# IR_beacon.net
KiCad netlist of a schematic drawn in EAGLE
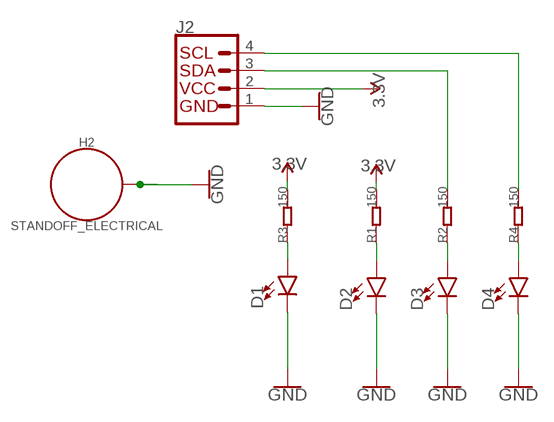
[diagram p0: schematic, sheet 1]

(export (version "E")
  (design (tool "Eeschema 10.0.6"))
  (components
    (comp (ref "D1")
      (value "LED-FKIT-1206")
      (footprint "eagle-import:FKIT-LED-1206")
      (libsource (lib "eagle-import") (part "LED-FKIT-1206"))
    )
    (comp (ref "D2")
      (value "LED-FKIT-1206")
      (footprint "eagle-import:FKIT-LED-1206")
      (libsource (lib "eagle-import") (part "LED-FKIT-1206"))
    )
    (comp (ref "D3")
      (value "LED-FKIT-1206")
      (footprint "eagle-import:FKIT-LED-1206")
      (libsource (lib "eagle-import") (part "LED-FKIT-1206"))
    )
    (comp (ref "D4")
      (value "LED-FKIT-1206")
      (footprint "eagle-import:FKIT-LED-1206")
      (libsource (lib "eagle-import") (part "LED-FKIT-1206"))
    )
    (comp (ref "H2")
      (value "STANDOFF_ELECTRICAL")
      (footprint "eagle-import:STANDOFF-ELECTRICAL")
      (libsource (lib "eagle-import") (part "STANDOFF_ELECTRICAL"))
    )
    (comp (ref "J2")
      (value "QWIIC_CONNECTORJS-1MM")
      (footprint "eagle-import:1X04_1MM_RA")
      (libsource (lib "eagle-import") (part "QWIIC_CONNECTORJS-1MM"))
    )
    (comp (ref "R1")
      (value "150")
      (footprint "eagle-import:0603_S")
      (libsource (lib "eagle-import") (part "005-R0603_S"))
    )
    (comp (ref "R2")
      (value "150")
      (footprint "eagle-import:0603_S")
      (libsource (lib "eagle-import") (part "005-R0603_S"))
    )
    (comp (ref "R3")
      (value "150")
      (footprint "eagle-import:0603_S")
      (libsource (lib "eagle-import") (part "005-R0603_S"))
    )
    (comp (ref "R4")
      (value "150")
      (footprint "eagle-import:0603_S")
      (libsource (lib "eagle-import") (part "005-R0603_S"))
    )
  )
  (nets
    (net (code "1") (name "3.3V") (class "Default")
      (node (ref "J2") (pin "2") (pinfunction "2_2") (pintype "power_in"))
      (node (ref "R1") (pin "2") (pinfunction "2_2") (pintype "passive"))
      (node (ref "R3") (pin "2") (pinfunction "2_2") (pintype "passive"))
    )
    (net (code "2") (name "GND") (class "Default")
      (node (ref "D1") (pin "C") (pinfunction "C_C") (pintype "passive"))
      (node (ref "D2") (pin "C") (pinfunction "C_C") (pintype "passive"))
      (node (ref "D3") (pin "C") (pinfunction "C_C") (pintype "passive"))
      (node (ref "D4") (pin "C") (pinfunction "C_C") (pintype "passive"))
      (node (ref "H2") (pin "P1") (pinfunction "P$1_P1") (pintype "bidirectional"))
      (node (ref "J2") (pin "1") (pinfunction "1_1") (pintype "power_in"))
    )
    (net (code "3") (name "Net-(D1-PadA)") (class "Default")
      (node (ref "D1") (pin "A") (pinfunction "A_A") (pintype "passive"))
      (node (ref "R3") (pin "1") (pinfunction "1_1") (pintype "passive"))
    )
    (net (code "4") (name "Net-(D2-PadA)") (class "Default")
      (node (ref "D2") (pin "A") (pinfunction "A_A") (pintype "passive"))
      (node (ref "R1") (pin "1") (pinfunction "1_1") (pintype "passive"))
    )
    (net (code "5") (name "Net-(D3-PadA)") (class "Default")
      (node (ref "D3") (pin "A") (pinfunction "A_A") (pintype "passive"))
      (node (ref "R2") (pin "1") (pinfunction "1_1") (pintype "passive"))
    )
    (net (code "6") (name "Net-(D4-PadA)") (class "Default")
      (node (ref "D4") (pin "A") (pinfunction "A_A") (pintype "passive"))
      (node (ref "R4") (pin "1") (pinfunction "1_1") (pintype "passive"))
    )
    (net (code "7") (name "Net-(J2-Pad3)") (class "Default")
      (node (ref "J2") (pin "3") (pinfunction "3_3") (pintype "passive"))
      (node (ref "R2") (pin "2") (pinfunction "2_2") (pintype "passive"))
    )
    (net (code "8") (name "Net-(J2-Pad4)") (class "Default")
      (node (ref "J2") (pin "4") (pinfunction "4_4") (pintype "passive"))
      (node (ref "R4") (pin "2") (pinfunction "2_2") (pintype "passive"))
    )
  )
)
